# PPG_Board.net
KiCad netlist of a schematic drawn in Altium Designer
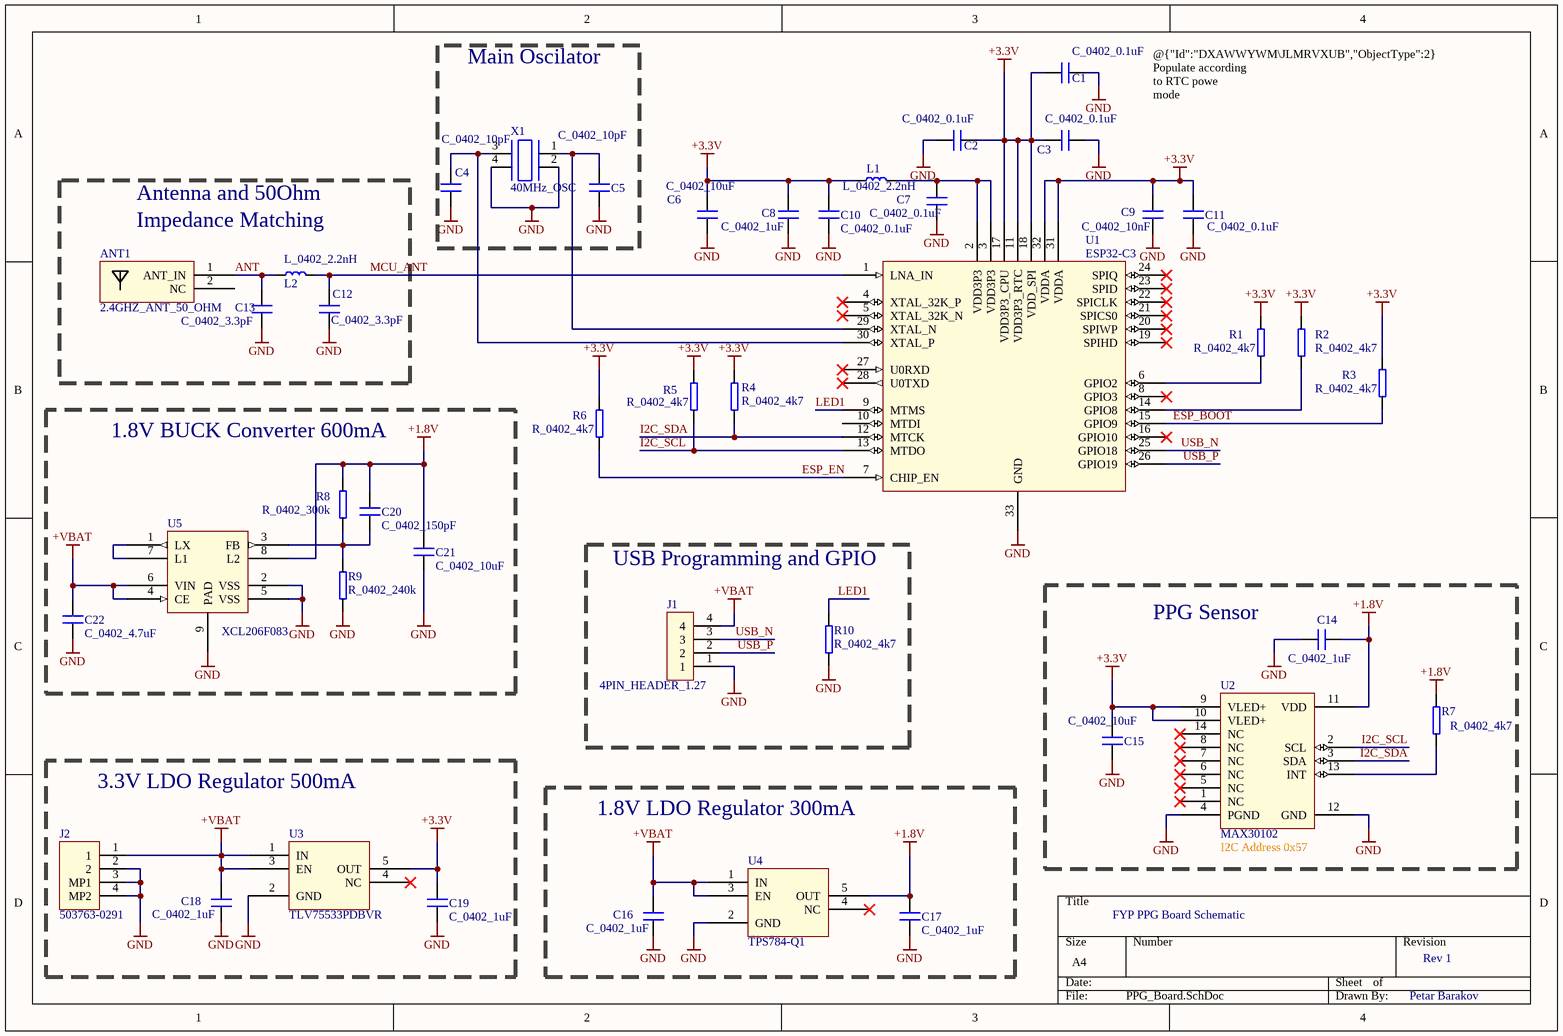
[diagram p0: PPG_Board.SchDoc]

(export (version "E")
  (design (tool "Eeschema 10.0.6"))
  (components
    (comp (ref "ANT1")
      (value "2.4GHZ_ANT_50_OHM")
      (footprint "Chip2PinSM127P600-8N")
      (description "2.4GHz Chip Antenna 50 Ohm Impedance ANT2012LL00R2400A")
      (libsource (lib "Petar B") (part "2.4GHZ_ANT_50_OHM"))
    )
    (comp (ref "C1")
      (value "C_0402_0.1uF")
      (footprint "C_0402")
      (fields (field (name "JLC PART NUMBER") "C1525"))
      (libsource (lib "Petar B") (part "Cap_symbol"))
    )
    (comp (ref "C2")
      (value "C_0402_0.1uF")
      (footprint "C_0402")
      (fields (field (name "JLC PART NUMBER") "C1525"))
      (libsource (lib "Petar B") (part "Cap_symbol"))
    )
    (comp (ref "C3")
      (value "C_0402_0.1uF")
      (footprint "C_0402")
      (fields (field (name "JLC PART NUMBER") "C1525"))
      (libsource (lib "Petar B") (part "Cap_symbol"))
    )
    (comp (ref "C4")
      (value "C_0402_10pF")
      (footprint "C_0402")
      (fields (field (name "JLC PART NUMBER") "C32949"))
      (libsource (lib "Petar B") (part "Cap_symbol"))
    )
    (comp (ref "C5")
      (value "C_0402_10pF")
      (footprint "C_0402")
      (fields (field (name "JLC PART NUMBER") "C32949"))
      (libsource (lib "Petar B") (part "Cap_symbol"))
    )
    (comp (ref "C6")
      (value "C_0402_10uF")
      (footprint "C_0402")
      (fields (field (name "JLC PART NUMBER") "C15525"))
      (libsource (lib "Petar B") (part "Cap_symbol"))
    )
    (comp (ref "C7")
      (value "C_0402_0.1uF")
      (footprint "C_0402")
      (fields (field (name "JLC PART NUMBER") "C1525"))
      (libsource (lib "Petar B") (part "Cap_symbol"))
    )
    (comp (ref "C8")
      (value "C_0402_1uF")
      (footprint "C_0402")
      (fields (field (name "JLC PART NUMBER") "C52923"))
      (libsource (lib "Petar B") (part "Cap_symbol"))
    )
    (comp (ref "C9")
      (value "C_0402_10nF")
      (footprint "C_0402")
      (fields (field (name "JLC PART NUMBER") "C15195"))
      (libsource (lib "Petar B") (part "Cap_symbol"))
    )
    (comp (ref "C10")
      (value "C_0402_0.1uF")
      (footprint "C_0402")
      (fields (field (name "JLC PART NUMBER") "C1525"))
      (libsource (lib "Petar B") (part "Cap_symbol"))
    )
    (comp (ref "C11")
      (value "C_0402_0.1uF")
      (footprint "C_0402")
      (fields (field (name "JLC PART NUMBER") "C1525"))
      (libsource (lib "Petar B") (part "Cap_symbol"))
    )
    (comp (ref "C12")
      (value "C_0402_3.3pF")
      (footprint "C_0402")
      (fields (field (name "JLC PART NUMBER") "C326841"))
      (libsource (lib "Petar B") (part "Cap_symbol"))
    )
    (comp (ref "C13")
      (value "C_0402_3.3pF")
      (footprint "C_0402")
      (fields (field (name "JLC PART NUMBER") "C326841"))
      (libsource (lib "Petar B") (part "Cap_symbol"))
    )
    (comp (ref "C14")
      (value "C_0402_1uF")
      (footprint "C_0402")
      (fields (field (name "JLC PART NUMBER") "C52923"))
      (libsource (lib "Petar B") (part "Cap_symbol"))
    )
    (comp (ref "C15")
      (value "C_0402_10uF")
      (footprint "C_0402")
      (fields (field (name "JLC PART NUMBER") "C15525"))
      (libsource (lib "Petar B") (part "Cap_symbol"))
    )
    (comp (ref "C16")
      (value "C_0402_1uF")
      (footprint "C_0402")
      (fields (field (name "JLC PART NUMBER") "C52923"))
      (libsource (lib "Petar B") (part "Cap_symbol"))
    )
    (comp (ref "C17")
      (value "C_0402_1uF")
      (footprint "C_0402")
      (fields (field (name "JLC PART NUMBER") "C52923"))
      (libsource (lib "Petar B") (part "Cap_symbol"))
    )
    (comp (ref "C18")
      (value "C_0402_1uF")
      (footprint "C_0402")
      (fields (field (name "JLC PART NUMBER") "C52923"))
      (libsource (lib "Petar B") (part "Cap_symbol"))
    )
    (comp (ref "C19")
      (value "C_0402_1uF")
      (footprint "C_0402")
      (fields (field (name "JLC PART NUMBER") "C52923"))
      (libsource (lib "Petar B") (part "Cap_symbol"))
    )
    (comp (ref "C20")
      (value "C_0402_150pF")
      (footprint "C_0402")
      (fields (field (name "JLC PART NUMBER") "C363531"))
      (libsource (lib "Petar B") (part "Cap_symbol"))
    )
    (comp (ref "C21")
      (value "C_0402_10uF")
      (footprint "C_0402")
      (fields (field (name "JLC PART NUMBER") "C15525"))
      (libsource (lib "Petar B") (part "Cap_symbol"))
    )
    (comp (ref "C22")
      (value "C_0402_4.7uF")
      (footprint "C_0402")
      (fields (field (name "JLC PART NUMBER") "C23733"))
      (libsource (lib "Petar B") (part "Cap_symbol"))
    )
    (comp (ref "J1")
      (value "4PIN_HEADER_1.27")
      (footprint "4PIN_HEADER_1.27-Footprint-1")
      (libsource (lib "Petar B") (part "4PIN_HEADER_1.27-Symbol-1"))
    )
    (comp (ref "J2")
      (value "503763-0291")
      (footprint "Molex 503763-0291")
      (description "Molex 503763-0291")
      (libsource (lib "Petar B") (part "503763-0291"))
    )
    (comp (ref "L1")
      (value "L_0402_2.2nH")
      (footprint "L_0402")
      (fields (field (name "JLC PART NUMBER") "C92035"))
      (libsource (lib "Petar B") (part "Ind_Symbol"))
    )
    (comp (ref "L2")
      (value "L_0402_2.2nH")
      (footprint "L_0402")
      (fields (field (name "JLC PART NUMBER") "C92035"))
      (libsource (lib "Petar B") (part "Ind_Symbol"))
    )
    (comp (ref "R1")
      (value "R_0402_4k7")
      (footprint "R_0402")
      (fields (field (name "JLC PART NUMBER") "C25900"))
      (libsource (lib "Petar B") (part "R_symbol"))
    )
    (comp (ref "R2")
      (value "R_0402_4k7")
      (footprint "R_0402")
      (fields (field (name "JLC PART NUMBER") "C25900"))
      (libsource (lib "Petar B") (part "R_symbol"))
    )
    (comp (ref "R3")
      (value "R_0402_4k7")
      (footprint "R_0402")
      (fields (field (name "JLC PART NUMBER") "C25900"))
      (libsource (lib "Petar B") (part "R_symbol"))
    )
    (comp (ref "R4")
      (value "R_0402_4k7")
      (footprint "R_0402")
      (fields (field (name "JLC PART NUMBER") "C25900"))
      (libsource (lib "Petar B") (part "R_symbol"))
    )
    (comp (ref "R5")
      (value "R_0402_4k7")
      (footprint "R_0402")
      (fields (field (name "JLC PART NUMBER") "C25900"))
      (libsource (lib "Petar B") (part "R_symbol"))
    )
    (comp (ref "R6")
      (value "R_0402_4k7")
      (footprint "R_0402")
      (fields (field (name "JLC PART NUMBER") "C25900"))
      (libsource (lib "Petar B") (part "R_symbol"))
    )
    (comp (ref "R7")
      (value "R_0402_4k7")
      (footprint "R_0402")
      (fields (field (name "JLC PART NUMBER") "C25900"))
      (libsource (lib "Petar B") (part "R_symbol"))
    )
    (comp (ref "R8")
      (value "R_0402_300k")
      (footprint "R_0402")
      (fields (field (name "JLC PART NUMBER") "C100363"))
      (libsource (lib "Petar B") (part "R_symbol"))
    )
    (comp (ref "R9")
      (value "R_0402_240k")
      (footprint "R_0402")
      (fields (field (name "JLC PART NUMBER") "C429390"))
      (libsource (lib "Petar B") (part "R_symbol"))
    )
    (comp (ref "R10")
      (value "R_0402_4k7")
      (footprint "R_0402")
      (fields (field (name "JLC PART NUMBER") "C25900"))
      (libsource (lib "Petar B") (part "R_symbol"))
    )
    (comp (ref "U1")
      (value "ESP32-C3")
      (footprint "QFN127P600-8N")
      (description "33 pin ESP32_C3 Microcontroller")
      (fields (field (name "JLC PART NUMBER") "C2858491"))
      (libsource (lib "Petar B") (part "ESP32-C3_symbol"))
    )
    (comp (ref "U2")
      (value "MAX30102")
      (footprint "MAX30102-Footprint-1")
      (description "Biometric Sensors Integrated Optical Sensor")
      (fields (field (name "JLC PART NUMBER") "C6454833"))
      (libsource (lib "Petar B") (part "MAX30102-Symbol-1"))
    )
    (comp (ref "U3")
      (value "TLV75533PDBVR")
      (footprint "SOT95P280X145-5N")
      (fields (field (name "JLC PART NUMBER") "C404027"))
      (libsource (lib "Petar B") (part "TLV75533PDBVR-Symbol"))
    )
    (comp (ref "U4")
      (value "TPS784-Q1")
      (footprint "SOT95P280X145-5N")
      (fields (field (name "JLC PART NUMBER") "C2877783"))
      (libsource (lib "Petar B") (part "TLV75533PDBVR-Symbol"))
    )
    (comp (ref "U5")
      (value "XCL206F083")
      (footprint "XCL206F083-Footprint-1")
      (description "Switching Voltage Regulators 600mA Inductor Built-in PWM Step-Down microDCDC Converter")
      (fields (field (name "JLC PART NUMBER") "C2891283"))
      (libsource (lib "Petar B") (part "XCL206F083-Symbol-1"))
    )
    (comp (ref "X1")
      (value "40MHz_OSC")
      (footprint "40MHz_OSC-Footprint-1")
      (description "40 MHZ Oscillator, 10pF load capacitance")
      (fields (field (name "JLC PART NUMBER") "C426988"))
      (libsource (lib "Petar B") (part "OSC_SYMB"))
    )
  )
  (nets
    (net (code "1") (name "+1.8V") (class "Default")
      (node (ref "C14") (pin "2") (pinfunction "2_2") (pintype "passive"))
      (node (ref "C17") (pin "2") (pinfunction "2_2") (pintype "passive"))
      (node (ref "C20") (pin "2") (pinfunction "2_2") (pintype "passive"))
      (node (ref "C21") (pin "2") (pinfunction "2_2") (pintype "passive"))
      (node (ref "R7") (pin "2") (pinfunction "2_2") (pintype "passive"))
      (node (ref "R8") (pin "1") (pinfunction "1_1") (pintype "passive"))
      (node (ref "U2") (pin "11") (pinfunction "VDD_11") (pintype "power_in"))
      (node (ref "U4") (pin "5") (pinfunction "OUT_5") (pintype "passive"))
      (node (ref "U5") (pin "8") (pinfunction "L2_8") (pintype "passive"))
    )
    (net (code "2") (name "+3.3V") (class "Default")
      (node (ref "C1") (pin "1") (pinfunction "1_1") (pintype "passive"))
      (node (ref "C10") (pin "1") (pinfunction "1_1") (pintype "passive"))
      (node (ref "C11") (pin "2") (pinfunction "2_2") (pintype "passive"))
      (node (ref "C15") (pin "2") (pinfunction "2_2") (pintype "passive"))
      (node (ref "C19") (pin "2") (pinfunction "2_2") (pintype "passive"))
      (node (ref "C2") (pin "2") (pinfunction "2_2") (pintype "passive"))
      (node (ref "C3") (pin "1") (pinfunction "1_1") (pintype "passive"))
      (node (ref "C6") (pin "2") (pinfunction "2_2") (pintype "passive"))
      (node (ref "C8") (pin "2") (pinfunction "2_2") (pintype "passive"))
      (node (ref "C9") (pin "2") (pinfunction "2_2") (pintype "passive"))
      (node (ref "L1") (pin "1") (pinfunction "1_1") (pintype "passive"))
      (node (ref "R1") (pin "1") (pinfunction "1_1") (pintype "passive"))
      (node (ref "R2") (pin "1") (pinfunction "1_1") (pintype "passive"))
      (node (ref "R3") (pin "1") (pinfunction "1_1") (pintype "passive"))
      (node (ref "R4") (pin "1") (pinfunction "1_1") (pintype "passive"))
      (node (ref "R5") (pin "1") (pinfunction "1_1") (pintype "passive"))
      (node (ref "R6") (pin "1") (pinfunction "1_1") (pintype "passive"))
      (node (ref "U1") (pin "11") (pinfunction "VDD3P3_RTC_11") (pintype "power_in"))
      (node (ref "U1") (pin "17") (pinfunction "VDD3P3_CPU_17") (pintype "power_in"))
      (node (ref "U1") (pin "18") (pinfunction "VDD_SPI_18") (pintype "power_in"))
      (node (ref "U1") (pin "31") (pinfunction "VDDA_31") (pintype "power_in"))
      (node (ref "U1") (pin "32") (pinfunction "VDDA_32") (pintype "power_in"))
      (node (ref "U2") (pin "10") (pinfunction "VLED+_10") (pintype "power_in"))
      (node (ref "U2") (pin "9") (pinfunction "VLED+_9") (pintype "power_in"))
      (node (ref "U3") (pin "5") (pinfunction "OUT_5") (pintype "passive"))
    )
    (net (code "3") (name "+VBAT") (class "Default")
      (node (ref "C16") (pin "2") (pinfunction "2_2") (pintype "passive"))
      (node (ref "C18") (pin "2") (pinfunction "2_2") (pintype "passive"))
      (node (ref "C22") (pin "2") (pinfunction "2_2") (pintype "passive"))
      (node (ref "J1") (pin "4") (pinfunction "4_4") (pintype "passive"))
      (node (ref "J2") (pin "1") (pinfunction "1_1") (pintype "passive"))
      (node (ref "U3") (pin "1") (pinfunction "IN_1") (pintype "passive"))
      (node (ref "U3") (pin "3") (pinfunction "EN_3") (pintype "passive"))
      (node (ref "U4") (pin "1") (pinfunction "IN_1") (pintype "passive"))
      (node (ref "U4") (pin "3") (pinfunction "EN_3") (pintype "passive"))
      (node (ref "U5") (pin "4") (pinfunction "CE_4") (pintype "input"))
      (node (ref "U5") (pin "6") (pinfunction "VIN_6") (pintype "power_in"))
    )
    (net (code "4") (name "/ANT") (class "Default")
      (node (ref "ANT1") (pin "1") (pinfunction "ANT_IN_1") (pintype "passive"))
      (node (ref "C13") (pin "2") (pinfunction "2_2") (pintype "passive"))
      (node (ref "L2") (pin "1") (pinfunction "1_1") (pintype "passive"))
    )
    (net (code "5") (name "/ESP_BOOT") (class "Default")
      (node (ref "R3") (pin "2") (pinfunction "2_2") (pintype "passive"))
      (node (ref "U1") (pin "15") (pinfunction "GPIO9_15") (pintype "bidirectional"))
    )
    (net (code "6") (name "/ESP_EN") (class "Default")
      (node (ref "R6") (pin "2") (pinfunction "2_2") (pintype "passive"))
      (node (ref "U1") (pin "7") (pinfunction "CHIP_EN_7") (pintype "input"))
    )
    (net (code "7") (name "/I2C_SCL") (class "Default")
      (node (ref "R5") (pin "2") (pinfunction "2_2") (pintype "passive"))
      (node (ref "U1") (pin "13") (pinfunction "MTDO_13") (pintype "bidirectional"))
      (node (ref "U2") (pin "2") (pinfunction "SCL_2") (pintype "bidirectional"))
    )
    (net (code "8") (name "/I2C_SDA") (class "Default")
      (node (ref "R4") (pin "2") (pinfunction "2_2") (pintype "passive"))
      (node (ref "U1") (pin "12") (pinfunction "MTCK_12") (pintype "bidirectional"))
      (node (ref "U2") (pin "3") (pinfunction "SDA_3") (pintype "bidirectional"))
    )
    (net (code "9") (name "/LED1") (class "Default")
      (node (ref "R10") (pin "1") (pinfunction "1_1") (pintype "passive"))
      (node (ref "U1") (pin "9") (pinfunction "MTMS_9") (pintype "bidirectional"))
    )
    (net (code "10") (name "/MCU_ANT") (class "Default")
      (node (ref "C12") (pin "2") (pinfunction "2_2") (pintype "passive"))
      (node (ref "L2") (pin "2") (pinfunction "2_2") (pintype "passive"))
      (node (ref "U1") (pin "1") (pinfunction "LNA_IN_1") (pintype "input"))
    )
    (net (code "11") (name "/USB_N") (class "Default")
      (node (ref "J1") (pin "3") (pinfunction "3_3") (pintype "passive"))
      (node (ref "U1") (pin "25") (pinfunction "GPIO18_25") (pintype "bidirectional"))
    )
    (net (code "12") (name "/USB_P") (class "Default")
      (node (ref "J1") (pin "2") (pinfunction "2_2") (pintype "passive"))
      (node (ref "U1") (pin "26") (pinfunction "GPIO19_26") (pintype "bidirectional"))
    )
    (net (code "13") (name "GND") (class "Default")
      (node (ref "C1") (pin "2") (pinfunction "2_2") (pintype "passive"))
      (node (ref "C10") (pin "2") (pinfunction "2_2") (pintype "passive"))
      (node (ref "C11") (pin "1") (pinfunction "1_1") (pintype "passive"))
      (node (ref "C12") (pin "1") (pinfunction "1_1") (pintype "passive"))
      (node (ref "C13") (pin "1") (pinfunction "1_1") (pintype "passive"))
      (node (ref "C14") (pin "1") (pinfunction "1_1") (pintype "passive"))
      (node (ref "C15") (pin "1") (pinfunction "1_1") (pintype "passive"))
      (node (ref "C16") (pin "1") (pinfunction "1_1") (pintype "passive"))
      (node (ref "C17") (pin "1") (pinfunction "1_1") (pintype "passive"))
      (node (ref "C18") (pin "1") (pinfunction "1_1") (pintype "passive"))
      (node (ref "C19") (pin "1") (pinfunction "1_1") (pintype "passive"))
      (node (ref "C2") (pin "1") (pinfunction "1_1") (pintype "passive"))
      (node (ref "C21") (pin "1") (pinfunction "1_1") (pintype "passive"))
      (node (ref "C22") (pin "1") (pinfunction "1_1") (pintype "passive"))
      (node (ref "C3") (pin "2") (pinfunction "2_2") (pintype "passive"))
      (node (ref "C4") (pin "1") (pinfunction "1_1") (pintype "passive"))
      (node (ref "C5") (pin "1") (pinfunction "1_1") (pintype "passive"))
      (node (ref "C6") (pin "1") (pinfunction "1_1") (pintype "passive"))
      (node (ref "C7") (pin "2") (pinfunction "2_2") (pintype "passive"))
      (node (ref "C8") (pin "1") (pinfunction "1_1") (pintype "passive"))
      (node (ref "C9") (pin "1") (pinfunction "1_1") (pintype "passive"))
      (node (ref "J1") (pin "1") (pinfunction "1_1") (pintype "passive"))
      (node (ref "J2") (pin "2") (pinfunction "2_2") (pintype "passive"))
      (node (ref "J2") (pin "3") (pinfunction "MP1_3") (pintype "passive"))
      (node (ref "J2") (pin "4") (pinfunction "MP2_4") (pintype "passive"))
      (node (ref "R10") (pin "2") (pinfunction "2_2") (pintype "passive"))
      (node (ref "R9") (pin "2") (pinfunction "2_2") (pintype "passive"))
      (node (ref "U1") (pin "33") (pinfunction "GND_33") (pintype "power_in"))
      (node (ref "U2") (pin "12") (pinfunction "GND_12") (pintype "power_in"))
      (node (ref "U2") (pin "4") (pinfunction "PGND_4") (pintype "power_in"))
      (node (ref "U3") (pin "2") (pinfunction "GND_2") (pintype "passive"))
      (node (ref "U4") (pin "2") (pinfunction "GND_2") (pintype "passive"))
      (node (ref "U5") (pin "2") (pinfunction "VSS_2") (pintype "power_in"))
      (node (ref "U5") (pin "5") (pinfunction "VSS_5") (pintype "power_in"))
      (node (ref "U5") (pin "9") (pinfunction "PAD_9") (pintype "power_in"))
      (node (ref "X1") (pin "2") (pinfunction "2_2") (pintype "passive"))
      (node (ref "X1") (pin "4") (pinfunction "4_4") (pintype "passive"))
    )
    (net (code "14") (name "Net-(C7-Pad1)") (class "Default")
      (node (ref "C7") (pin "1") (pinfunction "1_1") (pintype "passive"))
      (node (ref "L1") (pin "2") (pinfunction "2_2") (pintype "passive"))
      (node (ref "U1") (pin "2") (pinfunction "VDD3P3_2") (pintype "power_in"))
      (node (ref "U1") (pin "3") (pinfunction "VDD3P3_3") (pintype "power_in"))
    )
    (net (code "15") (name "Net-(U1-GPIO2)") (class "Default")
      (node (ref "R1") (pin "2") (pinfunction "2_2") (pintype "passive"))
      (node (ref "U1") (pin "6") (pinfunction "GPIO2_6") (pintype "bidirectional"))
    )
    (net (code "16") (name "Net-(U1-GPIO8)") (class "Default")
      (node (ref "R2") (pin "2") (pinfunction "2_2") (pintype "passive"))
      (node (ref "U1") (pin "14") (pinfunction "GPIO8_14") (pintype "bidirectional"))
    )
    (net (code "17") (name "Net-(U1-XTAL_N)") (class "Default")
      (node (ref "C5") (pin "2") (pinfunction "2_2") (pintype "passive"))
      (node (ref "U1") (pin "29") (pinfunction "XTAL_N_29") (pintype "bidirectional"))
      (node (ref "X1") (pin "1") (pinfunction "1_1") (pintype "passive"))
    )
    (net (code "18") (name "Net-(U1-XTAL_P)") (class "Default")
      (node (ref "C4") (pin "2") (pinfunction "2_2") (pintype "passive"))
      (node (ref "U1") (pin "30") (pinfunction "XTAL_P_30") (pintype "bidirectional"))
      (node (ref "X1") (pin "3") (pinfunction "3_3") (pintype "passive"))
    )
    (net (code "19") (name "Net-(U2-INT)") (class "Default")
      (node (ref "R7") (pin "1") (pinfunction "1_1") (pintype "passive"))
      (node (ref "U2") (pin "13") (pinfunction "INT_13") (pintype "bidirectional"))
    )
    (net (code "20") (name "Net-(U5-FB)") (class "Default")
      (node (ref "C20") (pin "1") (pinfunction "1_1") (pintype "passive"))
      (node (ref "R8") (pin "2") (pinfunction "2_2") (pintype "passive"))
      (node (ref "R9") (pin "1") (pinfunction "1_1") (pintype "passive"))
      (node (ref "U5") (pin "3") (pinfunction "FB_3") (pintype "output"))
    )
    (net (code "21") (name "Net-(U5-L1)") (class "Default")
      (node (ref "U5") (pin "1") (pinfunction "LX_1") (pintype "output"))
      (node (ref "U5") (pin "7") (pinfunction "L1_7") (pintype "passive"))
    )
    (net (code "22") (name "unconnected-(ANT1-NC-Pad2)") (class "Default")
      (node (ref "ANT1") (pin "2") (pinfunction "NC_2") (pintype "passive"))
    )
    (net (code "23") (name "unconnected-(U1-GPIO3-Pad8)") (class "Default")
      (node (ref "U1") (pin "8") (pinfunction "GPIO3_8") (pintype "bidirectional+no_connect"))
    )
    (net (code "24") (name "unconnected-(U1-GPIO10-Pad16)") (class "Default")
      (node (ref "U1") (pin "16") (pinfunction "GPIO10_16") (pintype "bidirectional+no_connect"))
    )
    (net (code "25") (name "unconnected-(U1-MTDI-Pad10)") (class "Default")
      (node (ref "U1") (pin "10") (pinfunction "MTDI_10") (pintype "bidirectional"))
    )
    (net (code "26") (name "unconnected-(U1-SPICLK-Pad22)") (class "Default")
      (node (ref "U1") (pin "22") (pinfunction "SPICLK_22") (pintype "bidirectional+no_connect"))
    )
    (net (code "27") (name "unconnected-(U1-SPICS0-Pad21)") (class "Default")
      (node (ref "U1") (pin "21") (pinfunction "SPICS0_21") (pintype "bidirectional+no_connect"))
    )
    (net (code "28") (name "unconnected-(U1-SPID-Pad23)") (class "Default")
      (node (ref "U1") (pin "23") (pinfunction "SPID_23") (pintype "bidirectional+no_connect"))
    )
    (net (code "29") (name "unconnected-(U1-SPIHD-Pad19)") (class "Default")
      (node (ref "U1") (pin "19") (pinfunction "SPIHD_19") (pintype "bidirectional+no_connect"))
    )
    (net (code "30") (name "unconnected-(U1-SPIQ-Pad24)") (class "Default")
      (node (ref "U1") (pin "24") (pinfunction "SPIQ_24") (pintype "bidirectional+no_connect"))
    )
    (net (code "31") (name "unconnected-(U1-SPIWP-Pad20)") (class "Default")
      (node (ref "U1") (pin "20") (pinfunction "SPIWP_20") (pintype "bidirectional+no_connect"))
    )
    (net (code "32") (name "unconnected-(U1-U0RXD-Pad27)") (class "Default")
      (node (ref "U1") (pin "27") (pinfunction "U0RXD_27") (pintype "input+no_connect"))
    )
    (net (code "33") (name "unconnected-(U1-U0TXD-Pad28)") (class "Default")
      (node (ref "U1") (pin "28") (pinfunction "U0TXD_28") (pintype "output+no_connect"))
    )
    (net (code "34") (name "unconnected-(U1-XTAL_32K_N-Pad5)") (class "Default")
      (node (ref "U1") (pin "5") (pinfunction "XTAL_32K_N_5") (pintype "bidirectional+no_connect"))
    )
    (net (code "35") (name "unconnected-(U1-XTAL_32K_P-Pad4)") (class "Default")
      (node (ref "U1") (pin "4") (pinfunction "XTAL_32K_P_4") (pintype "bidirectional+no_connect"))
    )
    (net (code "36") (name "unconnected-(U2-NC-Pad1)") (class "Default")
      (node (ref "U2") (pin "1") (pinfunction "NC_1") (pintype "passive+no_connect"))
    )
    (net (code "37") (name "unconnected-(U2-NC-Pad5)") (class "Default")
      (node (ref "U2") (pin "5") (pinfunction "NC_5") (pintype "passive+no_connect"))
    )
    (net (code "38") (name "unconnected-(U2-NC-Pad6)") (class "Default")
      (node (ref "U2") (pin "6") (pinfunction "NC_6") (pintype "passive+no_connect"))
    )
    (net (code "39") (name "unconnected-(U2-NC-Pad7)") (class "Default")
      (node (ref "U2") (pin "7") (pinfunction "NC_7") (pintype "passive+no_connect"))
    )
    (net (code "40") (name "unconnected-(U2-NC-Pad8)") (class "Default")
      (node (ref "U2") (pin "8") (pinfunction "NC_8") (pintype "passive+no_connect"))
    )
    (net (code "41") (name "unconnected-(U2-NC-Pad14)") (class "Default")
      (node (ref "U2") (pin "14") (pinfunction "NC_14") (pintype "passive+no_connect"))
    )
    (net (code "42") (name "unconnected-(U3-NC-Pad4)") (class "Default")
      (node (ref "U3") (pin "4") (pinfunction "NC_4") (pintype "passive+no_connect"))
    )
    (net (code "43") (name "unconnected-(U4-NC-Pad4)") (class "Default")
      (node (ref "U4") (pin "4") (pinfunction "NC_4") (pintype "passive+no_connect"))
    )
  )
)
